# hardware_design.net
KiCad netlist of a schematic drawn in Altium Designer
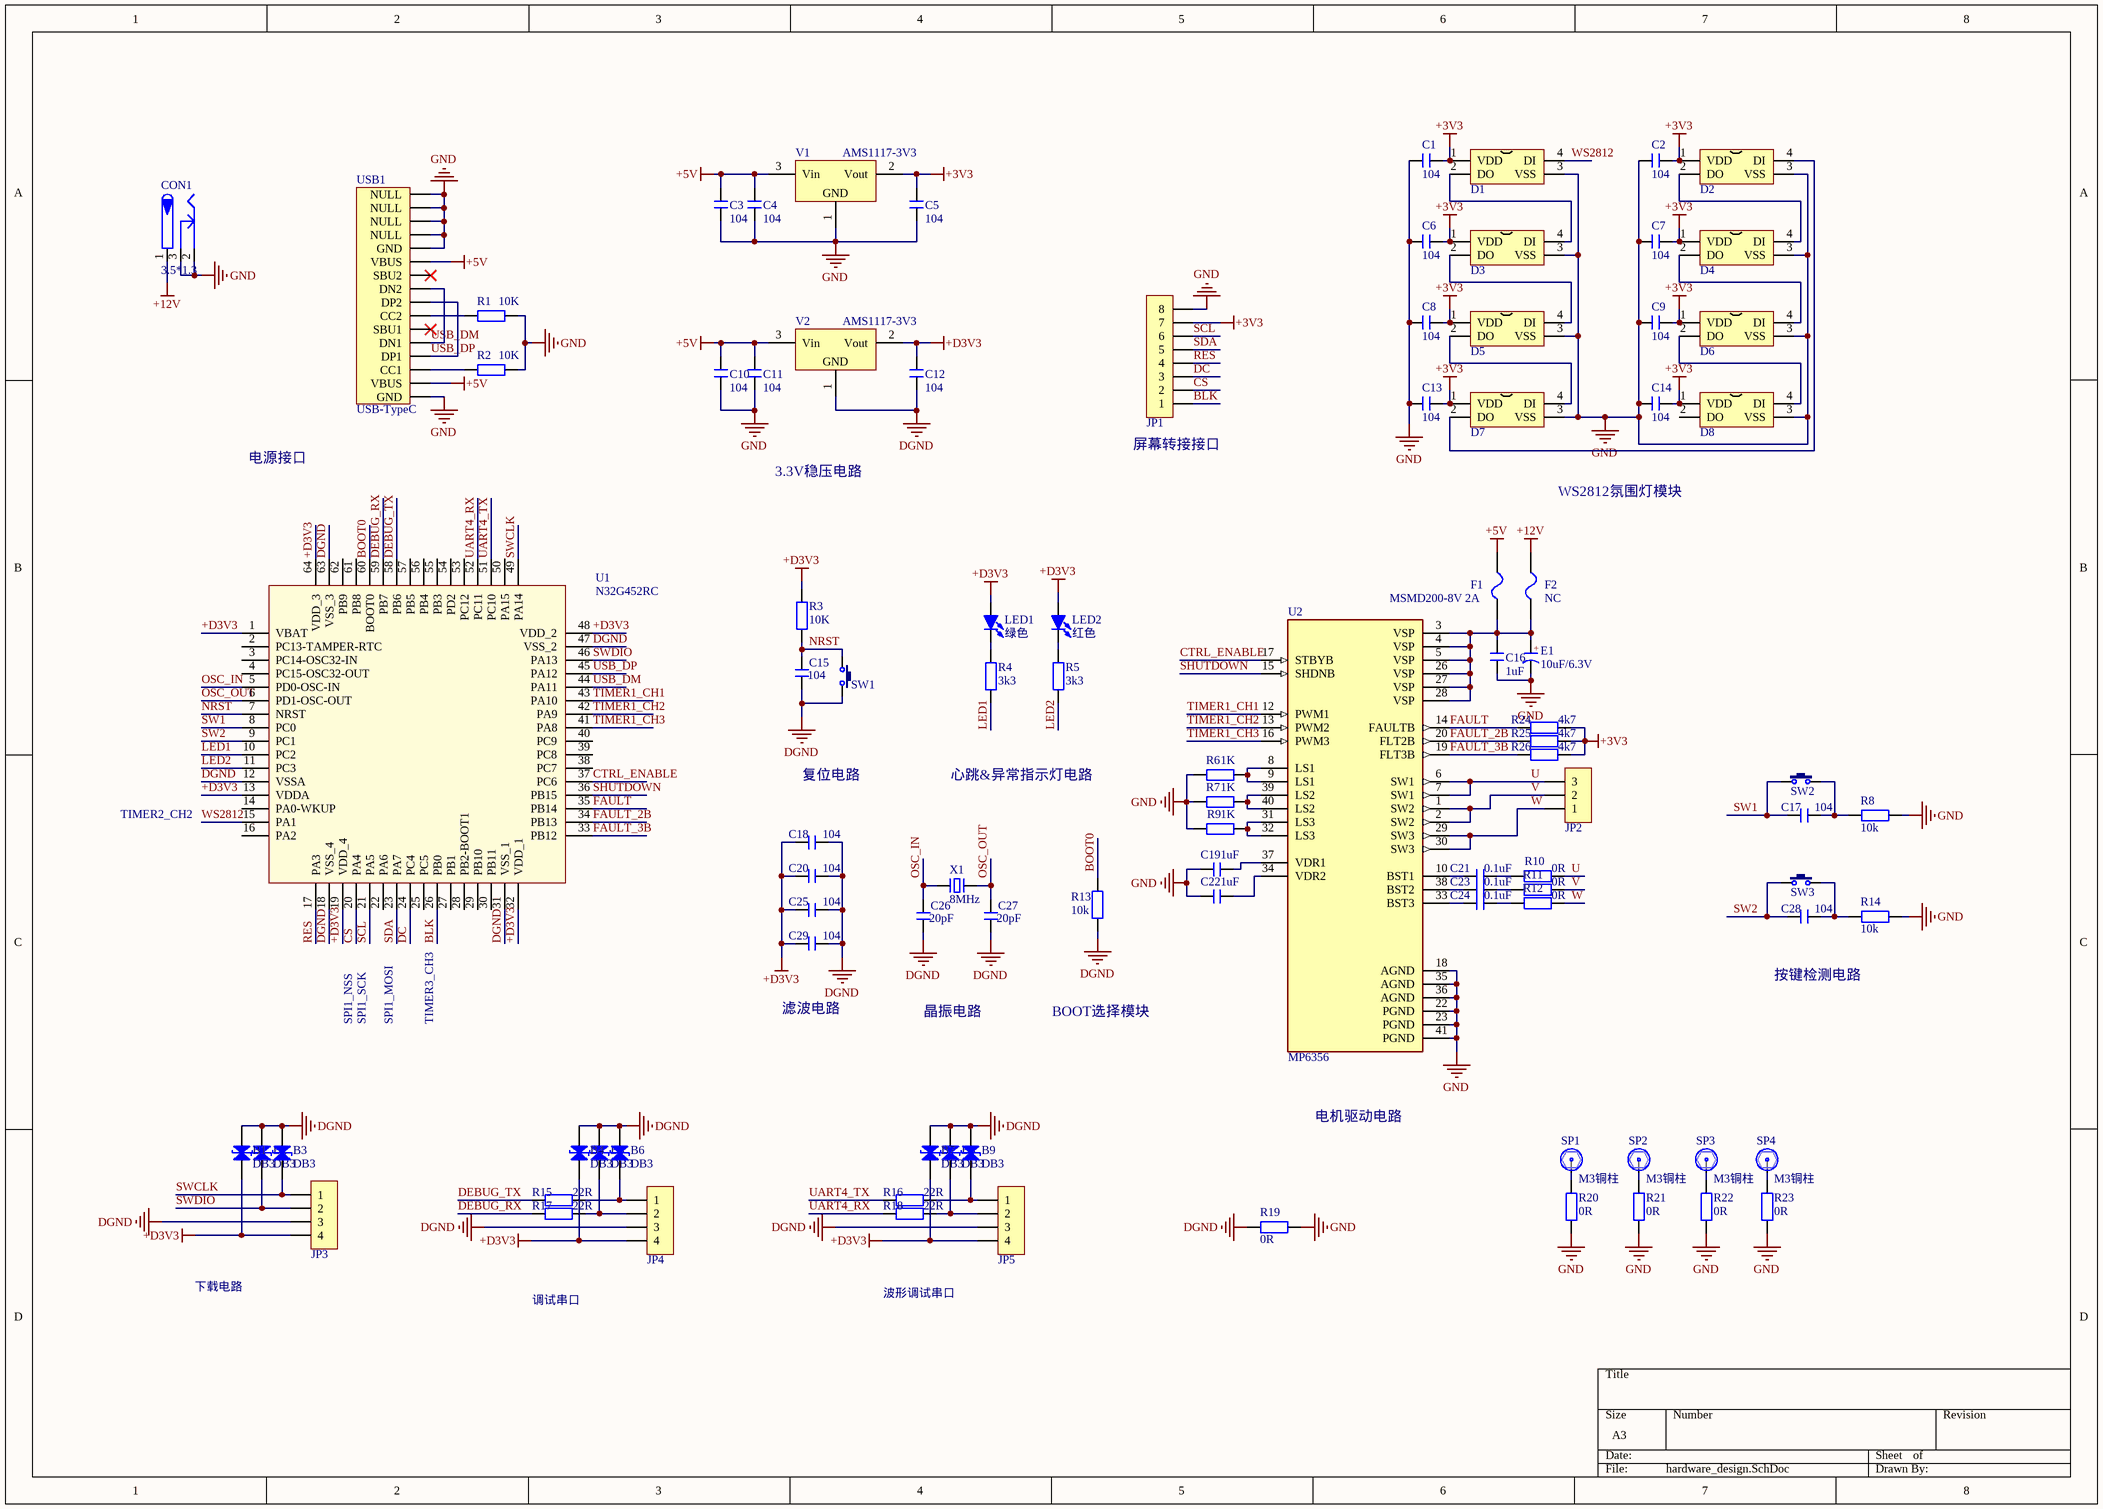
[diagram p0: hardware_design.SchDoc]

(export (version "E")
  (design (tool "Eeschema 10.0.6"))
  (components
    (comp (ref "B1")
      (value "DB3")
      (footprint "SOD-323")
      (description "双向触发二极管")
      (libsource (lib "8.1   - 二极管-整流桥") (part "DB3"))
    )
    (comp (ref "B2")
      (value "DB3")
      (footprint "SOD-323")
      (description "双向触发二极管")
      (libsource (lib "8.1   - 二极管-整流桥") (part "DB3"))
    )
    (comp (ref "B3")
      (value "DB3")
      (footprint "SOD-323")
      (description "双向触发二极管")
      (libsource (lib "8.1   - 二极管-整流桥") (part "DB3"))
    )
    (comp (ref "B4")
      (value "DB3")
      (footprint "SOD-323")
      (description "双向触发二极管")
      (libsource (lib "8.1   - 二极管-整流桥") (part "DB3"))
    )
    (comp (ref "B5")
      (value "DB3")
      (footprint "SOD-323")
      (description "双向触发二极管")
      (libsource (lib "8.1   - 二极管-整流桥") (part "DB3"))
    )
    (comp (ref "B6")
      (value "DB3")
      (footprint "SOD-323")
      (description "双向触发二极管")
      (libsource (lib "8.1   - 二极管-整流桥") (part "DB3"))
    )
    (comp (ref "B7")
      (value "DB3")
      (footprint "SOD-323")
      (description "双向触发二极管")
      (libsource (lib "8.1   - 二极管-整流桥") (part "DB3"))
    )
    (comp (ref "B8")
      (value "DB3")
      (footprint "SOD-323")
      (description "双向触发二极管")
      (libsource (lib "8.1   - 二极管-整流桥") (part "DB3"))
    )
    (comp (ref "B9")
      (value "DB3")
      (footprint "SOD-323")
      (description "双向触发二极管")
      (libsource (lib "8.1   - 二极管-整流桥") (part "DB3"))
    )
    (comp (ref "C1")
      (value "104")
      (footprint "C 0603_M")
      (description "无极性贴片电容")
      (fields (field (name "版权归属") "源创客"))
      (libsource (lib "3.1   - 电阻-电容-电感") (part "C"))
    )
    (comp (ref "C2")
      (value "104")
      (footprint "C 0603_M")
      (description "无极性贴片电容")
      (fields (field (name "版权归属") "源创客"))
      (libsource (lib "3.1   - 电阻-电容-电感") (part "C"))
    )
    (comp (ref "C3")
      (value "104")
      (footprint "C 0603_M")
      (description "无极性贴片电容")
      (fields (field (name "版权归属") "源创客"))
      (libsource (lib "3.1   - 电阻-电容-电感") (part "C"))
    )
    (comp (ref "C4")
      (value "104")
      (footprint "C 0603_M")
      (description "无极性贴片电容")
      (fields (field (name "版权归属") "源创客"))
      (libsource (lib "3.1   - 电阻-电容-电感") (part "C"))
    )
    (comp (ref "C5")
      (value "104")
      (footprint "C 0603_M")
      (description "无极性贴片电容")
      (fields (field (name "版权归属") "源创客"))
      (libsource (lib "3.1   - 电阻-电容-电感") (part "C"))
    )
    (comp (ref "C6")
      (value "104")
      (footprint "C 0603_M")
      (description "无极性贴片电容")
      (fields (field (name "版权归属") "源创客"))
      (libsource (lib "3.1   - 电阻-电容-电感") (part "C"))
    )
    (comp (ref "C7")
      (value "104")
      (footprint "C 0603_M")
      (description "无极性贴片电容")
      (fields (field (name "版权归属") "源创客"))
      (libsource (lib "3.1   - 电阻-电容-电感") (part "C"))
    )
    (comp (ref "C8")
      (value "104")
      (footprint "C 0603_M")
      (description "无极性贴片电容")
      (fields (field (name "版权归属") "源创客"))
      (libsource (lib "3.1   - 电阻-电容-电感") (part "C"))
    )
    (comp (ref "C9")
      (value "104")
      (footprint "C 0603_M")
      (description "无极性贴片电容")
      (fields (field (name "版权归属") "源创客"))
      (libsource (lib "3.1   - 电阻-电容-电感") (part "C"))
    )
    (comp (ref "C10")
      (value "104")
      (footprint "C 0603_M")
      (description "无极性贴片电容")
      (fields (field (name "版权归属") "源创客"))
      (libsource (lib "3.1   - 电阻-电容-电感") (part "C"))
    )
    (comp (ref "C11")
      (value "104")
      (footprint "C 0603_M")
      (description "无极性贴片电容")
      (fields (field (name "版权归属") "源创客"))
      (libsource (lib "3.1   - 电阻-电容-电感") (part "C"))
    )
    (comp (ref "C12")
      (value "104")
      (footprint "C 0603_M")
      (description "无极性贴片电容")
      (fields (field (name "版权归属") "源创客"))
      (libsource (lib "3.1   - 电阻-电容-电感") (part "C"))
    )
    (comp (ref "C13")
      (value "104")
      (footprint "C 0603_M")
      (description "无极性贴片电容")
      (fields (field (name "版权归属") "源创客"))
      (libsource (lib "3.1   - 电阻-电容-电感") (part "C"))
    )
    (comp (ref "C14")
      (value "104")
      (footprint "C 0603_M")
      (description "无极性贴片电容")
      (fields (field (name "版权归属") "源创客"))
      (libsource (lib "3.1   - 电阻-电容-电感") (part "C"))
    )
    (comp (ref "C15")
      (value "104")
      (footprint "C 0603_M")
      (description "无极性贴片电容")
      (fields (field (name "版权归属") "源创客"))
      (libsource (lib "3.1   - 电阻-电容-电感") (part "C"))
    )
    (comp (ref "C16")
      (value "1uF")
      (footprint "C 0603_M")
      (description "无极性贴片电容")
      (fields (field (name "版权归属") "源创客"))
      (libsource (lib "3.1   - 电阻-电容-电感") (part "C"))
    )
    (comp (ref "C17")
      (value "104")
      (footprint "C 0603_M")
      (description "无极性贴片电容")
      (fields (field (name "版权归属") "源创客"))
      (libsource (lib "3.1   - 电阻-电容-电感") (part "C"))
    )
    (comp (ref "C18")
      (value "104")
      (footprint "C 0603_M")
      (description "无极性贴片电容")
      (fields (field (name "版权归属") "源创客"))
      (libsource (lib "3.1   - 电阻-电容-电感") (part "C"))
    )
    (comp (ref "C19")
      (value "1uF")
      (footprint "C 0603_M")
      (description "无极性贴片电容")
      (fields (field (name "版权归属") "源创客"))
      (libsource (lib "3.1   - 电阻-电容-电感") (part "C"))
    )
    (comp (ref "C20")
      (value "104")
      (footprint "C 0603_M")
      (description "无极性贴片电容")
      (fields (field (name "版权归属") "源创客"))
      (libsource (lib "3.1   - 电阻-电容-电感") (part "C"))
    )
    (comp (ref "C21")
      (value "0.1uF")
      (footprint "C 0603_M")
      (description "无极性贴片电容")
      (fields (field (name "版权归属") "源创客"))
      (libsource (lib "3.1   - 电阻-电容-电感") (part "C"))
    )
    (comp (ref "C22")
      (value "1uF")
      (footprint "C 0603_M")
      (description "无极性贴片电容")
      (fields (field (name "版权归属") "源创客"))
      (libsource (lib "3.1   - 电阻-电容-电感") (part "C"))
    )
    (comp (ref "C23")
      (value "0.1uF")
      (footprint "C 0603_M")
      (description "无极性贴片电容")
      (fields (field (name "版权归属") "源创客"))
      (libsource (lib "3.1   - 电阻-电容-电感") (part "C"))
    )
    (comp (ref "C24")
      (value "0.1uF")
      (footprint "C 0603_M")
      (description "无极性贴片电容")
      (fields (field (name "版权归属") "源创客"))
      (libsource (lib "3.1   - 电阻-电容-电感") (part "C"))
    )
    (comp (ref "C25")
      (value "104")
      (footprint "C 0603_M")
      (description "无极性贴片电容")
      (fields (field (name "版权归属") "源创客"))
      (libsource (lib "3.1   - 电阻-电容-电感") (part "C"))
    )
    (comp (ref "C26")
      (value "20pF")
      (footprint "C 0603_M")
      (description "无极性贴片电容")
      (fields (field (name "版权归属") "源创客"))
      (libsource (lib "3.1   - 电阻-电容-电感") (part "C"))
    )
    (comp (ref "C27")
      (value "20pF")
      (footprint "C 0603_M")
      (description "无极性贴片电容")
      (fields (field (name "版权归属") "源创客"))
      (libsource (lib "3.1   - 电阻-电容-电感") (part "C"))
    )
    (comp (ref "C28")
      (value "104")
      (footprint "C 0603_M")
      (description "无极性贴片电容")
      (fields (field (name "版权归属") "源创客"))
      (libsource (lib "3.1   - 电阻-电容-电感") (part "C"))
    )
    (comp (ref "C29")
      (value "104")
      (footprint "C 0603_M")
      (description "无极性贴片电容")
      (fields (field (name "版权归属") "源创客"))
      (libsource (lib "3.1   - 电阻-电容-电感") (part "C"))
    )
    (comp (ref "CON1")
      (value "3.5*1.3")
      (footprint "DC-005")
      (description "低压电源接口")
      (fields (field (name "版权归属") "源创客"))
      (libsource (lib "4.1   - 接口类") (part "P-DC"))
    )
    (comp (ref "D1")
      (value "WS2812B")
      (footprint "WS2812 5050")
      (libsource (lib "9.1   - LED") (part "WS2812B"))
    )
    (comp (ref "D2")
      (value "WS2812B")
      (footprint "WS2812 5050")
      (libsource (lib "9.1   - LED") (part "WS2812B"))
    )
    (comp (ref "D3")
      (value "WS2812B")
      (footprint "WS2812 5050")
      (libsource (lib "9.1   - LED") (part "WS2812B"))
    )
    (comp (ref "D4")
      (value "WS2812B")
      (footprint "WS2812 5050")
      (libsource (lib "9.1   - LED") (part "WS2812B"))
    )
    (comp (ref "D5")
      (value "WS2812B")
      (footprint "WS2812 5050")
      (libsource (lib "9.1   - LED") (part "WS2812B"))
    )
    (comp (ref "D6")
      (value "WS2812B")
      (footprint "WS2812 5050")
      (libsource (lib "9.1   - LED") (part "WS2812B"))
    )
    (comp (ref "D7")
      (value "WS2812B")
      (footprint "WS2812 5050")
      (libsource (lib "9.1   - LED") (part "WS2812B"))
    )
    (comp (ref "D8")
      (value "WS2812B")
      (footprint "WS2812 5050")
      (libsource (lib "9.1   - LED") (part "WS2812B"))
    )
    (comp (ref "E1")
      (value "10uF/6.3V")
      (footprint "CD A(3216)")
      (description "贴片钽电容")
      (fields (field (name "版权归属") "源创客"))
      (libsource (lib "3.1   - 电阻-电容-电感") (part "C-CD"))
    )
    (comp (ref "F1")
      (value "MSMD200-8V 2A")
      (footprint "FU 1210")
      (description "贴片保险丝")
      (fields (field (name "版权归属") "源创客"))
      (libsource (lib "10.1 - 保险丝-晶振") (part "FU"))
    )
    (comp (ref "F2")
      (value "NC")
      (footprint "FU 1210")
      (description "贴片保险丝")
      (fields (field (name "版权归属") "源创客"))
      (libsource (lib "10.1 - 保险丝-晶振") (part "FU"))
    )
    (comp (ref "JP1")
      (value "HDR-1X8")
      (footprint "MX 1.25-WS-8P")
      (description "8P接插件")
      (fields (field (name "版权归属") "源创客"))
      (libsource (lib "4.2   - 接插件-脚距1.25") (part "Header 8"))
    )
    (comp (ref "JP2")
      (value "HDR-1X3")
      (footprint "XH2.54-WI-3P")
      (description "3P接插件")
      (fields (field (name "版权归属") "源创客"))
      (libsource (lib "4.5   - 接插件-脚距2.54") (part "Header 3"))
    )
    (comp (ref "JP3")
      (value "HDR-1X4")
      (footprint "MX 1.25-LS-4P")
      (description "4P接插件")
      (fields (field (name "版权归属") "源创客"))
      (libsource (lib "4.2   - 接插件-脚距1.25") (part "Header 4"))
    )
    (comp (ref "JP4")
      (value "HDR-1X4")
      (footprint "MX 1.25-LS-4P")
      (description "4P接插件")
      (fields (field (name "版权归属") "源创客"))
      (libsource (lib "4.2   - 接插件-脚距1.25") (part "Header 4"))
    )
    (comp (ref "JP5")
      (value "HDR-1X4")
      (footprint "MX 1.25-LS-4P")
      (description "4P接插件")
      (fields (field (name "版权归属") "源创客"))
      (libsource (lib "4.2   - 接插件-脚距1.25") (part "Header 4"))
    )
    (comp (ref "LED1")
      (value "绿色")
      (footprint "LED 0805W")
      (description "贴片LED")
      (fields (field (name "版权归属") "源创客"))
      (libsource (lib "9.1   - LED") (part "LED-SMD"))
    )
    (comp (ref "LED2")
      (value "红色")
      (footprint "LED 0805W")
      (description "贴片LED")
      (fields (field (name "版权归属") "源创客"))
      (libsource (lib "9.1   - LED") (part "LED-SMD"))
    )
    (comp (ref "R1")
      (value "10K")
      (footprint "R 0805_M")
      (description "贴片电阻")
      (fields (field (name "版权归属") "源创客"))
      (libsource (lib "3.1   - 电阻-电容-电感") (part "R"))
    )
    (comp (ref "R2")
      (value "10K")
      (footprint "R 0805_M")
      (description "贴片电阻")
      (fields (field (name "版权归属") "源创客"))
      (libsource (lib "3.1   - 电阻-电容-电感") (part "R"))
    )
    (comp (ref "R3")
      (value "10K")
      (footprint "R 0603_M")
      (description "贴片电阻")
      (fields (field (name "版权归属") "源创客"))
      (libsource (lib "3.1   - 电阻-电容-电感") (part "R"))
    )
    (comp (ref "R4")
      (value "3k3")
      (footprint "R 0603_M")
      (description "贴片电阻")
      (fields (field (name "版权归属") "源创客"))
      (libsource (lib "3.1   - 电阻-电容-电感") (part "R"))
    )
    (comp (ref "R5")
      (value "3k3")
      (footprint "R 0603_M")
      (description "贴片电阻")
      (fields (field (name "版权归属") "源创客"))
      (libsource (lib "3.1   - 电阻-电容-电感") (part "R"))
    )
    (comp (ref "R6")
      (value "1K")
      (footprint "R 1210_M")
      (description "贴片电阻")
      (fields (field (name "版权归属") "源创客"))
      (libsource (lib "3.1   - 电阻-电容-电感") (part "R"))
    )
    (comp (ref "R7")
      (value "1K")
      (footprint "R 1210_M")
      (description "贴片电阻")
      (fields (field (name "版权归属") "源创客"))
      (libsource (lib "3.1   - 电阻-电容-电感") (part "R"))
    )
    (comp (ref "R8")
      (value "10k")
      (footprint "R 0603_M")
      (description "贴片电阻")
      (fields (field (name "版权归属") "源创客"))
      (libsource (lib "3.1   - 电阻-电容-电感") (part "R"))
    )
    (comp (ref "R9")
      (value "1K")
      (footprint "R 1210_M")
      (description "贴片电阻")
      (fields (field (name "版权归属") "源创客"))
      (libsource (lib "3.1   - 电阻-电容-电感") (part "R"))
    )
    (comp (ref "R10")
      (value "0R")
      (footprint "R 0603_M")
      (description "贴片电阻")
      (fields (field (name "版权归属") "源创客"))
      (libsource (lib "3.1   - 电阻-电容-电感") (part "R"))
    )
    (comp (ref "R11")
      (value "0R")
      (footprint "R 0603_M")
      (description "贴片电阻")
      (fields (field (name "版权归属") "源创客"))
      (libsource (lib "3.1   - 电阻-电容-电感") (part "R"))
    )
    (comp (ref "R12")
      (value "0R")
      (footprint "R 0603_M")
      (description "贴片电阻")
      (fields (field (name "版权归属") "源创客"))
      (libsource (lib "3.1   - 电阻-电容-电感") (part "R"))
    )
    (comp (ref "R13")
      (value "10k")
      (footprint "R 0603_M")
      (description "贴片电阻")
      (fields (field (name "版权归属") "源创客"))
      (libsource (lib "3.1   - 电阻-电容-电感") (part "R"))
    )
    (comp (ref "R14")
      (value "10k")
      (footprint "R 0603_M")
      (description "贴片电阻")
      (fields (field (name "版权归属") "源创客"))
      (libsource (lib "3.1   - 电阻-电容-电感") (part "R"))
    )
    (comp (ref "R15")
      (value "22R")
      (footprint "R 0603_M")
      (description "贴片电阻")
      (fields (field (name "版权归属") "源创客"))
      (libsource (lib "3.1   - 电阻-电容-电感") (part "R"))
    )
    (comp (ref "R16")
      (value "22R")
      (footprint "R 0603_M")
      (description "贴片电阻")
      (fields (field (name "版权归属") "源创客"))
      (libsource (lib "3.1   - 电阻-电容-电感") (part "R"))
    )
    (comp (ref "R17")
      (value "22R")
      (footprint "R 0603_M")
      (description "贴片电阻")
      (fields (field (name "版权归属") "源创客"))
      (libsource (lib "3.1   - 电阻-电容-电感") (part "R"))
    )
    (comp (ref "R18")
      (value "22R")
      (footprint "R 0603_M")
      (description "贴片电阻")
      (fields (field (name "版权归属") "源创客"))
      (libsource (lib "3.1   - 电阻-电容-电感") (part "R"))
    )
    (comp (ref "R19")
      (value "0R")
      (footprint "R 0603_M")
      (description "贴片电阻")
      (fields (field (name "版权归属") "源创客"))
      (libsource (lib "3.1   - 电阻-电容-电感") (part "R"))
    )
    (comp (ref "R20")
      (value "0R")
      (footprint "R 0603_M")
      (description "贴片电阻")
      (fields (field (name "版权归属") "源创客"))
      (libsource (lib "3.1   - 电阻-电容-电感") (part "R"))
    )
    (comp (ref "R21")
      (value "0R")
      (footprint "R 0603_M")
      (description "贴片电阻")
      (fields (field (name "版权归属") "源创客"))
      (libsource (lib "3.1   - 电阻-电容-电感") (part "R"))
    )
    (comp (ref "R22")
      (value "0R")
      (footprint "R 0603_M")
      (description "贴片电阻")
      (fields (field (name "版权归属") "源创客"))
      (libsource (lib "3.1   - 电阻-电容-电感") (part "R"))
    )
    (comp (ref "R23")
      (value "0R")
      (footprint "R 0603_M")
      (description "贴片电阻")
      (fields (field (name "版权归属") "源创客"))
      (libsource (lib "3.1   - 电阻-电容-电感") (part "R"))
    )
    (comp (ref "R24")
      (value "4k7")
      (footprint "R 0603_M")
      (description "贴片电阻")
      (fields (field (name "版权归属") "源创客"))
      (libsource (lib "3.1   - 电阻-电容-电感") (part "R"))
    )
    (comp (ref "R25")
      (value "4k7")
      (footprint "R 0603_M")
      (description "贴片电阻")
      (fields (field (name "版权归属") "源创客"))
      (libsource (lib "3.1   - 电阻-电容-电感") (part "R"))
    )
    (comp (ref "R26")
      (value "4k7")
      (footprint "R 0603_M")
      (description "贴片电阻")
      (fields (field (name "版权归属") "源创客"))
      (libsource (lib "3.1   - 电阻-电容-电感") (part "R"))
    )
    (comp (ref "SP1")
      (value "M3铜柱")
      (footprint "M3x4_L")
      (description "铜柱")
      (fields (field (name "版权归属") "源创客"))
      (libsource (lib "library") (part "铜柱小焊盘"))
    )
    (comp (ref "SP2")
      (value "M3铜柱")
      (footprint "M3x4_L")
      (description "铜柱")
      (fields (field (name "版权归属") "源创客"))
      (libsource (lib "library") (part "铜柱小焊盘"))
    )
    (comp (ref "SP3")
      (value "M3铜柱")
      (footprint "M3x4_L")
      (description "铜柱")
      (fields (field (name "版权归属") "源创客"))
      (libsource (lib "library") (part "铜柱小焊盘"))
    )
    (comp (ref "SP4")
      (value "M3铜柱")
      (footprint "M3x4_L")
      (description "铜柱")
      (fields (field (name "版权归属") "源创客"))
      (libsource (lib "library") (part "铜柱小焊盘"))
    )
    (comp (ref "SW1")
      (value "3x6x5")
      (footprint "TSW SMD-3*6*2.5")
      (description "3x6轻触开关")
      (fields (field (name "版权归属") "源创客"))
      (libsource (lib "5.1   - 按键-开关") (part "TSW 3x6"))
    )
    (comp (ref "SW2")
      (value "3x6x5")
      (footprint "TSW SMD-3*6*2.5")
      (description "3x6轻触开关")
      (fields (field (name "版权归属") "源创客"))
      (libsource (lib "") (part "TSW 3x6_1"))
    )
    (comp (ref "SW3")
      (value "3x6x5")
      (footprint "TSW SMD-3*6*2.5")
      (description "3x6轻触开关")
      (fields (field (name "版权归属") "源创客"))
      (libsource (lib "") (part "TSW 3x6_1"))
    )
    (comp (ref "U1")
      (value "N32G452RC")
      (footprint "LQFP64-10*10")
      (description "国民技术32位mcu IO64")
      (libsource (lib "library") (part "N32G452RC"))
    )
    (comp (ref "U2")
      (value "MP6356")
      (footprint "QFN40（5x5mm）")
      (description "直流无刷电机驱动IC")
      (libsource (lib "library") (part "MP6536DU-LF-P"))
    )
    (comp (ref "USB1")
      (value "USB-TypeC")
      (footprint "USB-TypeC-16Pin")
      (description "TypeC 16pin")
      (libsource (lib "library") (part "USB-TypeC-16Pin"))
    )
    (comp (ref "V1")
      (value "AMS1117-3V3")
      (footprint "SOT223_M")
      (description "三端稳压芯片")
      (fields (field (name "版权归属") "源创客"))
      (libsource (lib "1.3   - 电源类芯片") (part "AMS1117"))
    )
    (comp (ref "V2")
      (value "AMS1117-3V3")
      (footprint "SOT223_M")
      (description "三端稳压芯片")
      (fields (field (name "版权归属") "源创客"))
      (libsource (lib "1.3   - 电源类芯片") (part "AMS1117"))
    )
    (comp (ref "X1")
      (value "8MHz")
      (footprint "OSC HC-49SMD")
      (description "2脚无源脚晶振")
      (fields (field (name "版权归属") "源创客"))
      (libsource (lib "10.1 - 保险丝-晶振") (part "XTAL-2P"))
    )
  )
  (nets
    (net (code "1") (name "+3V3") (class "Default")
      (node (ref "C1") (pin "1") (pinfunction "1_1") (pintype "passive"))
      (node (ref "C13") (pin "1") (pinfunction "1_1") (pintype "passive"))
      (node (ref "C14") (pin "1") (pinfunction "1_1") (pintype "passive"))
      (node (ref "C2") (pin "1") (pinfunction "1_1") (pintype "passive"))
      (node (ref "C5") (pin "1") (pinfunction "1_1") (pintype "passive"))
      (node (ref "C6") (pin "1") (pinfunction "1_1") (pintype "passive"))
      (node (ref "C7") (pin "1") (pinfunction "1_1") (pintype "passive"))
      (node (ref "C8") (pin "1") (pinfunction "1_1") (pintype "passive"))
      (node (ref "C9") (pin "1") (pinfunction "1_1") (pintype "passive"))
      (node (ref "D1") (pin "1") (pinfunction "VDD_1") (pintype "passive"))
      (node (ref "D2") (pin "1") (pinfunction "VDD_1") (pintype "passive"))
      (node (ref "D3") (pin "1") (pinfunction "VDD_1") (pintype "passive"))
      (node (ref "D4") (pin "1") (pinfunction "VDD_1") (pintype "passive"))
      (node (ref "D5") (pin "1") (pinfunction "VDD_1") (pintype "passive"))
      (node (ref "D6") (pin "1") (pinfunction "VDD_1") (pintype "passive"))
      (node (ref "D7") (pin "1") (pinfunction "VDD_1") (pintype "passive"))
      (node (ref "D8") (pin "1") (pinfunction "VDD_1") (pintype "passive"))
      (node (ref "JP1") (pin "7") (pinfunction "7_7") (pintype "passive"))
      (node (ref "R24") (pin "2") (pinfunction "2_2") (pintype "passive"))
      (node (ref "R25") (pin "2") (pinfunction "2_2") (pintype "passive"))
      (node (ref "R26") (pin "2") (pinfunction "2_2") (pintype "passive"))
      (node (ref "V1") (pin "2") (pinfunction "Vout_2") (pintype "passive"))
    )
    (net (code "2") (name "+5V") (class "Default")
      (node (ref "C10") (pin "1") (pinfunction "1_1") (pintype "passive"))
      (node (ref "C11") (pin "1") (pinfunction "1_1") (pintype "passive"))
      (node (ref "C3") (pin "1") (pinfunction "1_1") (pintype "passive"))
      (node (ref "C4") (pin "1") (pinfunction "1_1") (pintype "passive"))
      (node (ref "F1") (pin "1") (pinfunction "1_1") (pintype "passive"))
      (node (ref "USB1") (pin "A4B9") (pinfunction "VBUS_A4B9") (pintype "passive"))
      (node (ref "USB1") (pin "B4A9") (pinfunction "VBUS_B4A9") (pintype "passive"))
      (node (ref "V1") (pin "3") (pinfunction "Vin_3") (pintype "passive"))
      (node (ref "V2") (pin "3") (pinfunction "Vin_3") (pintype "passive"))
    )
    (net (code "3") (name "+12V") (class "Default")
      (node (ref "CON1") (pin "1") (pintype "power_in"))
      (node (ref "F2") (pin "2") (pinfunction "2_2") (pintype "passive"))
    )
    (net (code "4") (name "+D3V3") (class "Default")
      (node (ref "B1") (pin "2") (pinfunction "K_2") (pintype "passive"))
      (node (ref "B4") (pin "2") (pinfunction "K_2") (pintype "passive"))
      (node (ref "B7") (pin "2") (pinfunction "K_2") (pintype "passive"))
      (node (ref "C12") (pin "1") (pinfunction "1_1") (pintype "passive"))
      (node (ref "C18") (pin "2") (pinfunction "2_2") (pintype "passive"))
      (node (ref "C20") (pin "2") (pinfunction "2_2") (pintype "passive"))
      (node (ref "C25") (pin "2") (pinfunction "2_2") (pintype "passive"))
      (node (ref "C29") (pin "2") (pinfunction "2_2") (pintype "passive"))
      (node (ref "JP3") (pin "4") (pinfunction "4_4") (pintype "passive"))
      (node (ref "JP4") (pin "4") (pinfunction "4_4") (pintype "passive"))
      (node (ref "JP5") (pin "4") (pinfunction "4_4") (pintype "passive"))
      (node (ref "LED1") (pin "1") (pinfunction "A_1") (pintype "passive"))
      (node (ref "LED2") (pin "1") (pinfunction "A_1") (pintype "passive"))
      (node (ref "R3") (pin "2") (pinfunction "2_2") (pintype "passive"))
      (node (ref "U1") (pin "1") (pinfunction "VBAT_1") (pintype "passive"))
      (node (ref "U1") (pin "13") (pinfunction "VDDA_13") (pintype "passive"))
      (node (ref "U1") (pin "19") (pinfunction "VDD_4_19") (pintype "passive"))
      (node (ref "U1") (pin "32") (pinfunction "VDD_1_32") (pintype "passive"))
      (node (ref "U1") (pin "48") (pinfunction "VDD_2_48") (pintype "passive"))
      (node (ref "U1") (pin "64") (pinfunction "VDD_3_64") (pintype "passive"))
      (node (ref "V2") (pin "2") (pinfunction "Vout_2") (pintype "passive"))
    )
    (net (code "5") (name "/BLK") (class "Default")
      (node (ref "JP1") (pin "1") (pinfunction "1_1") (pintype "passive"))
      (node (ref "U1") (pin "26") (pinfunction "PB0_26") (pintype "passive"))
    )
    (net (code "6") (name "/BOOT0") (class "Default")
      (node (ref "R13") (pin "2") (pinfunction "2_2") (pintype "passive"))
      (node (ref "U1") (pin "60") (pinfunction "BOOT0_60") (pintype "passive"))
    )
    (net (code "7") (name "/CS") (class "Default")
      (node (ref "JP1") (pin "2") (pinfunction "2_2") (pintype "passive"))
      (node (ref "U1") (pin "20") (pinfunction "PA4_20") (pintype "passive"))
    )
    (net (code "8") (name "/CTRL_ENABLE") (class "Default")
      (node (ref "U1") (pin "37") (pinfunction "PC6_37") (pintype "passive"))
      (node (ref "U2") (pin "17") (pinfunction "STBYB_17") (pintype "input"))
    )
    (net (code "9") (name "/DC") (class "Default")
      (node (ref "JP1") (pin "3") (pinfunction "3_3") (pintype "passive"))
      (node (ref "U1") (pin "24") (pinfunction "PC4_24") (pintype "passive"))
    )
    (net (code "10") (name "/DEBUG_RX") (class "Default")
      (node (ref "R17") (pin "1") (pinfunction "1_1") (pintype "passive"))
      (node (ref "U1") (pin "59") (pinfunction "PB7_59") (pintype "passive"))
    )
    (net (code "11") (name "/DEBUG_TX") (class "Default")
      (node (ref "R15") (pin "1") (pinfunction "1_1") (pintype "passive"))
      (node (ref "U1") (pin "58") (pinfunction "PB6_58") (pintype "passive"))
    )
    (net (code "12") (name "/FAULT") (class "Default")
      (node (ref "R24") (pin "1") (pinfunction "1_1") (pintype "passive"))
      (node (ref "U1") (pin "35") (pinfunction "PB14_35") (pintype "passive"))
      (node (ref "U2") (pin "14") (pinfunction "FAULTB_14") (pintype "output"))
    )
    (net (code "13") (name "/FAULT_2B") (class "Default")
      (node (ref "R25") (pin "1") (pinfunction "1_1") (pintype "passive"))
      (node (ref "U1") (pin "34") (pinfunction "PB13_34") (pintype "passive"))
      (node (ref "U2") (pin "20") (pinfunction "FLT2B_20") (pintype "output"))
    )
    (net (code "14") (name "/FAULT_3B") (class "Default")
      (node (ref "R26") (pin "1") (pinfunction "1_1") (pintype "passive"))
      (node (ref "U1") (pin "33") (pinfunction "PB12_33") (pintype "passive"))
      (node (ref "U2") (pin "19") (pinfunction "FLT3B_19") (pintype "output"))
    )
    (net (code "15") (name "/LED1") (class "Default")
      (node (ref "R4") (pin "1") (pinfunction "1_1") (pintype "passive"))
      (node (ref "U1") (pin "10") (pinfunction "PC2_10") (pintype "passive"))
    )
    (net (code "16") (name "/LED2") (class "Default")
      (node (ref "R5") (pin "1") (pinfunction "1_1") (pintype "passive"))
      (node (ref "U1") (pin "11") (pinfunction "PC3_11") (pintype "passive"))
    )
    (net (code "17") (name "/NRST") (class "Default")
      (node (ref "C15") (pin "2") (pinfunction "2_2") (pintype "passive"))
      (node (ref "R3") (pin "1") (pinfunction "1_1") (pintype "passive"))
      (node (ref "SW1") (pin "1") (pinfunction "1_1") (pintype "passive"))
      (node (ref "U1") (pin "7") (pinfunction "NRST_7") (pintype "passive"))
    )
    (net (code "18") (name "/OSC_IN") (class "Default")
      (node (ref "C26") (pin "2") (pinfunction "2_2") (pintype "passive"))
      (node (ref "U1") (pin "5") (pinfunction "PD0-OSC-IN_5") (pintype "passive"))
      (node (ref "X1") (pin "1") (pinfunction "1_1") (pintype "passive"))
    )
    (net (code "19") (name "/OSC_OUT") (class "Default")
      (node (ref "C27") (pin "2") (pinfunction "2_2") (pintype "passive"))
      (node (ref "U1") (pin "6") (pinfunction "PD1-OSC-OUT_6") (pintype "passive"))
      (node (ref "X1") (pin "2") (pinfunction "2_2") (pintype "passive"))
    )
    (net (code "20") (name "/RES") (class "Default")
      (node (ref "JP1") (pin "4") (pinfunction "4_4") (pintype "passive"))
      (node (ref "U1") (pin "17") (pinfunction "PA3_17") (pintype "passive"))
    )
    (net (code "21") (name "/SCL") (class "Default")
      (node (ref "JP1") (pin "6") (pinfunction "6_6") (pintype "passive"))
      (node (ref "U1") (pin "21") (pinfunction "PA5_21") (pintype "passive"))
    )
    (net (code "22") (name "/SDA") (class "Default")
      (node (ref "JP1") (pin "5") (pinfunction "5_5") (pintype "passive"))
      (node (ref "U1") (pin "23") (pinfunction "PA7_23") (pintype "passive"))
    )
    (net (code "23") (name "/SHUTDOWN") (class "Default")
      (node (ref "U1") (pin "36") (pinfunction "PB15_36") (pintype "passive"))
      (node (ref "U2") (pin "15") (pinfunction "SHDNB_15") (pintype "input"))
    )
    (net (code "24") (name "/SW1") (class "Default")
      (node (ref "C17") (pin "2") (pinfunction "2_2") (pintype "passive"))
      (node (ref "SW2") (pin "1") (pinfunction "1_1") (pintype "passive"))
      (node (ref "U1") (pin "8") (pinfunction "PC0_8") (pintype "passive"))
    )
    (net (code "25") (name "/SW2") (class "Default")
      (node (ref "C28") (pin "2") (pinfunction "2_2") (pintype "passive"))
      (node (ref "SW3") (pin "1") (pinfunction "1_1") (pintype "passive"))
      (node (ref "U1") (pin "9") (pinfunction "PC1_9") (pintype "passive"))
    )
    (net (code "26") (name "/SWCLK") (class "Default")
      (node (ref "B3") (pin "2") (pinfunction "K_2") (pintype "passive"))
      (node (ref "JP3") (pin "1") (pinfunction "1_1") (pintype "passive"))
      (node (ref "U1") (pin "49") (pinfunction "PA14_49") (pintype "passive"))
    )
    (net (code "27") (name "/SWDIO") (class "Default")
      (node (ref "B2") (pin "2") (pinfunction "K_2") (pintype "passive"))
      (node (ref "JP3") (pin "2") (pinfunction "2_2") (pintype "passive"))
      (node (ref "U1") (pin "46") (pinfunction "PA13_46") (pintype "passive"))
    )
    (net (code "28") (name "/TIMER1_CH1") (class "Default")
      (node (ref "U1") (pin "43") (pinfunction "PA10_43") (pintype "passive"))
      (node (ref "U2") (pin "12") (pinfunction "PWM1_12") (pintype "input"))
    )
    (net (code "29") (name "/TIMER1_CH2") (class "Default")
      (node (ref "U1") (pin "42") (pinfunction "PA9_42") (pintype "passive"))
      (node (ref "U2") (pin "13") (pinfunction "PWM2_13") (pintype "input"))
    )
    (net (code "30") (name "/TIMER1_CH3") (class "Default")
      (node (ref "U1") (pin "41") (pinfunction "PA8_41") (pintype "passive"))
      (node (ref "U2") (pin "16") (pinfunction "PWM3_16") (pintype "input"))
    )
    (net (code "31") (name "/U") (class "Default")
      (node (ref "JP2") (pin "3") (pinfunction "3_3") (pintype "passive"))
      (node (ref "R10") (pin "2") (pinfunction "2_2") (pintype "passive"))
      (node (ref "U2") (pin "6") (pinfunction "SW1_6") (pintype "output"))
      (node (ref "U2") (pin "7") (pinfunction "SW1_7") (pintype "output"))
    )
    (net (code "32") (name "/UART4_RX") (class "Default")
      (node (ref "R18") (pin "1") (pinfunction "1_1") (pintype "passive"))
      (node (ref "U1") (pin "52") (pinfunction "PC11_52") (pintype "passive"))
    )
    (net (code "33") (name "/UART4_TX") (class "Default")
      (node (ref "R16") (pin "1") (pinfunction "1_1") (pintype "passive"))
      (node (ref "U1") (pin "51") (pinfunction "PC10_51") (pintype "passive"))
    )
    (net (code "34") (name "/USB_DM") (class "Default")
      (node (ref "U1") (pin "44") (pinfunction "PA11_44") (pintype "passive"))
      (node (ref "USB1") (pin "A7") (pinfunction "DN1_A7") (pintype "passive"))
      (node (ref "USB1") (pin "B7") (pinfunction "DN2_B7") (pintype "passive"))
    )
    (net (code "35") (name "/USB_DP") (class "Default")
      (node (ref "U1") (pin "45") (pinfunction "PA12_45") (pintype "passive"))
      (node (ref "USB1") (pin "A6") (pinfunction "DP1_A6") (pintype "passive"))
      (node (ref "USB1") (pin "B6") (pinfunction "DP2_B6") (pintype "passive"))
    )
    (net (code "36") (name "/V") (class "Default")
      (node (ref "JP2") (pin "2") (pinfunction "2_2") (pintype "passive"))
      (node (ref "R11") (pin "2") (pinfunction "2_2") (pintype "passive"))
      (node (ref "U2") (pin "1") (pinfunction "SW2_1") (pintype "output"))
      (node (ref "U2") (pin "2") (pinfunction "SW2_2") (pintype "output"))
    )
    (net (code "37") (name "/W") (class "Default")
      (node (ref "JP2") (pin "1") (pinfunction "1_1") (pintype "passive"))
      (node (ref "R12") (pin "2") (pinfunction "2_2") (pintype "passive"))
      (node (ref "U2") (pin "29") (pinfunction "SW3_29") (pintype "output"))
      (node (ref "U2") (pin "30") (pinfunction "SW3_30") (pintype "output"))
    )
    (net (code "38") (name "/WS2812") (class "Default")
      (node (ref "D1") (pin "4") (pinfunction "DI_4") (pintype "passive"))
      (node (ref "U1") (pin "15") (pinfunction "PA1_15") (pintype "passive"))
    )
    (net (code "39") (name "DGND") (class "Default")
      (node (ref "B1") (pin "1") (pinfunction "A_1") (pintype "passive"))
      (node (ref "B2") (pin "1") (pinfunction "A_1") (pintype "passive"))
      (node (ref "B3") (pin "1") (pinfunction "A_1") (pintype "passive"))
      (node (ref "B4") (pin "1") (pinfunction "A_1") (pintype "passive"))
      (node (ref "B5") (pin "1") (pinfunction "A_1") (pintype "passive"))
      (node (ref "B6") (pin "1") (pinfunction "A_1") (pintype "passive"))
      (node (ref "B7") (pin "1") (pinfunction "A_1") (pintype "passive"))
      (node (ref "B8") (pin "1") (pinfunction "A_1") (pintype "passive"))
      (node (ref "B9") (pin "1") (pinfunction "A_1") (pintype "passive"))
      (node (ref "C12") (pin "2") (pinfunction "2_2") (pintype "passive"))
      (node (ref "C15") (pin "1") (pinfunction "1_1") (pintype "passive"))
      (node (ref "C18") (pin "1") (pinfunction "1_1") (pintype "passive"))
      (node (ref "C20") (pin "1") (pinfunction "1_1") (pintype "passive"))
      (node (ref "C25") (pin "1") (pinfunction "1_1") (pintype "passive"))
      (node (ref "C26") (pin "1") (pinfunction "1_1") (pintype "passive"))
      (node (ref "C27") (pin "1") (pinfunction "1_1") (pintype "passive"))
      (node (ref "C29") (pin "1") (pinfunction "1_1") (pintype "passive"))
      (node (ref "JP3") (pin "3") (pinfunction "3_3") (pintype "passive"))
      (node (ref "JP4") (pin "3") (pinfunction "3_3") (pintype "passive"))
      (node (ref "JP5") (pin "3") (pinfunction "3_3") (pintype "passive"))
      (node (ref "R13") (pin "1") (pinfunction "1_1") (pintype "passive"))
      (node (ref "R19") (pin "1") (pinfunction "1_1") (pintype "passive"))
      (node (ref "SW1") (pin "2") (pinfunction "2_2") (pintype "passive"))
      (node (ref "U1") (pin "12") (pinfunction "VSSA_12") (pintype "passive"))
      (node (ref "U1") (pin "18") (pinfunction "VSS_4_18") (pintype "passive"))
      (node (ref "U1") (pin "31") (pinfunction "VSS_1_31") (pintype "passive"))
      (node (ref "U1") (pin "47") (pinfunction "VSS_2_47") (pintype "passive"))
      (node (ref "U1") (pin "63") (pinfunction "VSS_3_63") (pintype "passive"))
      (node (ref "V2") (pin "1") (pinfunction "GND_1") (pintype "passive"))
    )
    (net (code "40") (name "GND") (class "Default")
      (node (ref "C1") (pin "2") (pinfunction "2_2") (pintype "passive"))
      (node (ref "C10") (pin "2") (pinfunction "2_2") (pintype "passive"))
      (node (ref "C11") (pin "2") (pinfunction "2_2") (pintype "passive"))
      (node (ref "C13") (pin "2") (pinfunction "2_2") (pintype "passive"))
      (node (ref "C14") (pin "2") (pinfunction "2_2") (pintype "passive"))
      (node (ref "C16") (pin "2") (pinfunction "2_2") (pintype "passive"))
      (node (ref "C19") (pin "1") (pinfunction "1_1") (pintype "passive"))
      (node (ref "C2") (pin "2") (pinfunction "2_2") (pintype "passive"))
      (node (ref "C22") (pin "1") (pinfunction "1_1") (pintype "passive"))
      (node (ref "C3") (pin "2") (pinfunction "2_2") (pintype "passive"))
      (node (ref "C4") (pin "2") (pinfunction "2_2") (pintype "passive"))
      (node (ref "C5") (pin "2") (pinfunction "2_2") (pintype "passive"))
      (node (ref "C6") (pin "2") (pinfunction "2_2") (pintype "passive"))
      (node (ref "C7") (pin "2") (pinfunction "2_2") (pintype "passive"))
      (node (ref "C8") (pin "2") (pinfunction "2_2") (pintype "passive"))
      (node (ref "C9") (pin "2") (pinfunction "2_2") (pintype "passive"))
      (node (ref "CON1") (pin "2") (pintype "power_in"))
      (node (ref "CON1") (pin "3") (pintype "power_in"))
      (node (ref "D1") (pin "3") (pinfunction "VSS_3") (pintype "passive"))
      (node (ref "D2") (pin "3") (pinfunction "VSS_3") (pintype "passive"))
      (node (ref "D3") (pin "3") (pinfunction "VSS_3") (pintype "passive"))
      (node (ref "D4") (pin "3") (pinfunction "VSS_3") (pintype "passive"))
      (node (ref "D5") (pin "3") (pinfunction "VSS_3") (pintype "passive"))
      (node (ref "D6") (pin "3") (pinfunction "VSS_3") (pintype "passive"))
      (node (ref "D7") (pin "3") (pinfunction "VSS_3") (pintype "passive"))
      (node (ref "D8") (pin "3") (pinfunction "VSS_3") (pintype "passive"))
      (node (ref "E1") (pin "2") (pinfunction "K_2") (pintype "passive"))
      (node (ref "JP1") (pin "8") (pinfunction "8_8") (pintype "passive"))
      (node (ref "R1") (pin "2") (pinfunction "2_2") (pintype "passive"))
      (node (ref "R14") (pin "1") (pinfunction "1_1") (pintype "passive"))
      (node (ref "R19") (pin "2") (pinfunction "2_2") (pintype "passive"))
      (node (ref "R2") (pin "2") (pinfunction "2_2") (pintype "passive"))
      (node (ref "R20") (pin "2") (pinfunction "2_2") (pintype "passive"))
      (node (ref "R21") (pin "2") (pinfunction "2_2") (pintype "passive"))
      (node (ref "R22") (pin "2") (pinfunction "2_2") (pintype "passive"))
      (node (ref "R23") (pin "2") (pinfunction "2_2") (pintype "passive"))
      (node (ref "R6") (pin "1") (pinfunction "1_1") (pintype "passive"))
      (node (ref "R7") (pin "1") (pinfunction "1_1") (pintype "passive"))
      (node (ref "R8") (pin "1") (pinfunction "1_1") (pintype "passive"))
      (node (ref "R9") (pin "1") (pinfunction "1_1") (pintype "passive"))
      (node (ref "U2") (pin "18") (pinfunction "AGND_18") (pintype "power_in"))
      (node (ref "U2") (pin "22") (pinfunction "PGND_22") (pintype "power_in"))
      (node (ref "U2") (pin "23") (pinfunction "PGND_23") (pintype "power_in"))
      (node (ref "U2") (pin "35") (pinfunction "AGND_35") (pintype "power_in"))
      (node (ref "U2") (pin "36") (pinfunction "AGND_36") (pintype "power_in"))
      (node (ref "U2") (pin "41") (pinfunction "PGND_41") (pintype "power_in"))
      (node (ref "USB1") (pin "1") (pinfunction "NULL_1") (pintype "passive"))
      (node (ref "USB1") (pin "2") (pinfunction "NULL_2") (pintype "passive"))
      (node (ref "USB1") (pin "3") (pinfunction "NULL_3") (pintype "passive"))
      (node (ref "USB1") (pin "4") (pinfunction "NULL_4") (pintype "passive"))
      (node (ref "USB1") (pin "A1B12") (pinfunction "GND_A1B12") (pintype "passive"))
      (node (ref "USB1") (pin "B1A12") (pinfunction "GND_B1A12") (pintype "passive"))
      (node (ref "V1") (pin "1") (pinfunction "GND_1") (pintype "passive"))
    )
    (net (code "41") (name "Net-(B5-K)") (class "Default")
      (node (ref "B5") (pin "2") (pinfunction "K_2") (pintype "passive"))
      (node (ref "JP4") (pin "2") (pinfunction "2_2") (pintype "passive"))
      (node (ref "R17") (pin "2") (pinfunction "2_2") (pintype "passive"))
    )
    (net (code "42") (name "Net-(B6-K)") (class "Default")
      (node (ref "B6") (pin "2") (pinfunction "K_2") (pintype "passive"))
      (node (ref "JP4") (pin "1") (pinfunction "1_1") (pintype "passive"))
      (node (ref "R15") (pin "2") (pinfunction "2_2") (pintype "passive"))
    )
    (net (code "43") (name "Net-(B8-K)") (class "Default")
      (node (ref "B8") (pin "2") (pinfunction "K_2") (pintype "passive"))
      (node (ref "JP5") (pin "2") (pinfunction "2_2") (pintype "passive"))
      (node (ref "R18") (pin "2") (pinfunction "2_2") (pintype "passive"))
    )
    (net (code "44") (name "Net-(B9-K)") (class "Default")
      (node (ref "B9") (pin "2") (pinfunction "K_2") (pintype "passive"))
      (node (ref "JP5") (pin "1") (pinfunction "1_1") (pintype "passive"))
      (node (ref "R16") (pin "2") (pinfunction "2_2") (pintype "passive"))
    )
    (net (code "45") (name "Net-(C17-Pad1)") (class "Default")
      (node (ref "C17") (pin "1") (pinfunction "1_1") (pintype "passive"))
      (node (ref "R8") (pin "2") (pinfunction "2_2") (pintype "passive"))
      (node (ref "SW2") (pin "2") (pinfunction "2_2") (pintype "passive"))
    )
    (net (code "46") (name "Net-(C21-Pad2)") (class "Default")
      (node (ref "C21") (pin "2") (pinfunction "2_2") (pintype "passive"))
      (node (ref "R10") (pin "1") (pinfunction "1_1") (pintype "passive"))
    )
    (net (code "47") (name "Net-(C23-Pad2)") (class "Default")
      (node (ref "C23") (pin "2") (pinfunction "2_2") (pintype "passive"))
      (node (ref "R11") (pin "1") (pinfunction "1_1") (pintype "passive"))
    )
    (net (code "48") (name "Net-(C24-Pad2)") (class "Default")
      (node (ref "C24") (pin "2") (pinfunction "2_2") (pintype "passive"))
      (node (ref "R12") (pin "1") (pinfunction "1_1") (pintype "passive"))
    )
    (net (code "49") (name "Net-(C28-Pad1)") (class "Default")
      (node (ref "C28") (pin "1") (pinfunction "1_1") (pintype "passive"))
      (node (ref "R14") (pin "2") (pinfunction "2_2") (pintype "passive"))
      (node (ref "SW3") (pin "2") (pinfunction "2_2") (pintype "passive"))
    )
    (net (code "50") (name "Net-(D1-DO)") (class "Default")
      (node (ref "D1") (pin "2") (pinfunction "DO_2") (pintype "passive"))
      (node (ref "D3") (pin "4") (pinfunction "DI_4") (pintype "passive"))
    )
    (net (code "51") (name "Net-(D2-DI)") (class "Default")
      (node (ref "D2") (pin "4") (pinfunction "DI_4") (pintype "passive"))
      (node (ref "D7") (pin "2") (pinfunction "DO_2") (pintype "passive"))
    )
    (net (code "52") (name "Net-(D2-DO)") (class "Default")
      (node (ref "D2") (pin "2") (pinfunction "DO_2") (pintype "passive"))
      (node (ref "D4") (pin "4") (pinfunction "DI_4") (pintype "passive"))
    )
    (net (code "53") (name "Net-(D3-DO)") (class "Default")
      (node (ref "D3") (pin "2") (pinfunction "DO_2") (pintype "passive"))
      (node (ref "D5") (pin "4") (pinfunction "DI_4") (pintype "passive"))
    )
    (net (code "54") (name "Net-(D4-DO)") (class "Default")
      (node (ref "D4") (pin "2") (pinfunction "DO_2") (pintype "passive"))
      (node (ref "D6") (pin "4") (pinfunction "DI_4") (pintype "passive"))
    )
    (net (code "55") (name "Net-(D5-DO)") (class "Default")
      (node (ref "D5") (pin "2") (pinfunction "DO_2") (pintype "passive"))
      (node (ref "D7") (pin "4") (pinfunction "DI_4") (pintype "passive"))
    )
    (net (code "56") (name "Net-(D6-DO)") (class "Default")
      (node (ref "D6") (pin "2") (pinfunction "DO_2") (pintype "passive"))
      (node (ref "D8") (pin "4") (pinfunction "DI_4") (pintype "passive"))
    )
    (net (code "57") (name "Net-(E1-A)") (class "Default")
      (node (ref "C16") (pin "1") (pinfunction "1_1") (pintype "passive"))
      (node (ref "E1") (pin "1") (pinfunction "A_1") (pintype "passive"))
      (node (ref "F1") (pin "2") (pinfunction "2_2") (pintype "passive"))
      (node (ref "F2") (pin "1") (pinfunction "1_1") (pintype "passive"))
      (node (ref "U2") (pin "26") (pinfunction "VSP_26") (pintype "power_in"))
      (node (ref "U2") (pin "27") (pinfunction "VSP_27") (pintype "power_in"))
      (node (ref "U2") (pin "28") (pinfunction "VSP_28") (pintype "power_in"))
      (node (ref "U2") (pin "3") (pinfunction "VSP_3") (pintype "power_in"))
      (node (ref "U2") (pin "4") (pinfunction "VSP_4") (pintype "power_in"))
      (node (ref "U2") (pin "5") (pinfunction "VSP_5") (pintype "power_in"))
    )
    (net (code "58") (name "Net-(LED1-K)") (class "Default")
      (node (ref "LED1") (pin "2") (pinfunction "K_2") (pintype "passive"))
      (node (ref "R4") (pin "2") (pinfunction "2_2") (pintype "passive"))
    )
    (net (code "59") (name "Net-(LED2-K)") (class "Default")
      (node (ref "LED2") (pin "2") (pinfunction "K_2") (pintype "passive"))
      (node (ref "R5") (pin "2") (pinfunction "2_2") (pintype "passive"))
    )
    (net (code "60") (name "Net-(R6-Pad2)") (class "Default")
      (node (ref "R6") (pin "2") (pinfunction "2_2") (pintype "passive"))
      (node (ref "U2") (pin "8") (pinfunction "LS1_8") (pintype "passive"))
      (node (ref "U2") (pin "9") (pinfunction "LS1_9") (pintype "passive"))
    )
    (net (code "61") (name "Net-(R7-Pad2)") (class "Default")
      (node (ref "R7") (pin "2") (pinfunction "2_2") (pintype "passive"))
      (node (ref "U2") (pin "39") (pinfunction "LS2_39") (pintype "passive"))
      (node (ref "U2") (pin "40") (pinfunction "LS2_40") (pintype "passive"))
    )
    (net (code "62") (name "Net-(R9-Pad2)") (class "Default")
      (node (ref "R9") (pin "2") (pinfunction "2_2") (pintype "passive"))
      (node (ref "U2") (pin "31") (pinfunction "LS3_31") (pintype "passive"))
      (node (ref "U2") (pin "32") (pinfunction "LS3_32") (pintype "passive"))
    )
    (net (code "63") (name "Net-(R20-Pad1)") (class "Default")
      (node (ref "R20") (pin "1") (pinfunction "1_1") (pintype "passive"))
      (node (ref "SP1") (pin "1") (pinfunction "1_1") (pintype "passive"))
    )
    (net (code "64") (name "Net-(R21-Pad1)") (class "Default")
      (node (ref "R21") (pin "1") (pinfunction "1_1") (pintype "passive"))
      (node (ref "SP2") (pin "1") (pinfunction "1_1") (pintype "passive"))
    )
    (net (code "65") (name "Net-(R22-Pad1)") (class "Default")
      (node (ref "R22") (pin "1") (pinfunction "1_1") (pintype "passive"))
      (node (ref "SP3") (pin "1") (pinfunction "1_1") (pintype "passive"))
    )
    (net (code "66") (name "Net-(R23-Pad1)") (class "Default")
      (node (ref "R23") (pin "1") (pinfunction "1_1") (pintype "passive"))
      (node (ref "SP4") (pin "1") (pinfunction "1_1") (pintype "passive"))
    )
    (net (code "67") (name "Net-(U2-BST1)") (class "Default")
      (node (ref "C21") (pin "1") (pinfunction "1_1") (pintype "passive"))
      (node (ref "U2") (pin "10") (pinfunction "BST1_10") (pintype "passive"))
    )
    (net (code "68") (name "Net-(U2-BST2)") (class "Default")
      (node (ref "C23") (pin "1") (pinfunction "1_1") (pintype "passive"))
      (node (ref "U2") (pin "38") (pinfunction "BST2_38") (pintype "passive"))
    )
    (net (code "69") (name "Net-(U2-BST3)") (class "Default")
      (node (ref "C24") (pin "1") (pinfunction "1_1") (pintype "passive"))
      (node (ref "U2") (pin "33") (pinfunction "BST3_33") (pintype "passive"))
    )
    (net (code "70") (name "Net-(U2-VDR1)") (class "Default")
      (node (ref "C19") (pin "2") (pinfunction "2_2") (pintype "passive"))
      (node (ref "U2") (pin "37") (pinfunction "VDR1_37") (pintype "passive"))
    )
    (net (code "71") (name "Net-(U2-VDR2)") (class "Default")
      (node (ref "C22") (pin "2") (pinfunction "2_2") (pintype "passive"))
      (node (ref "U2") (pin "34") (pinfunction "VDR2_34") (pintype "passive"))
    )
    (net (code "72") (name "Net-(USB1-CC1)") (class "Default")
      (node (ref "R2") (pin "1") (pinfunction "1_1") (pintype "passive"))
      (node (ref "USB1") (pin "A5") (pinfunction "CC1_A5") (pintype "passive"))
    )
    (net (code "73") (name "Net-(USB1-CC2)") (class "Default")
      (node (ref "R1") (pin "1") (pinfunction "1_1") (pintype "passive"))
      (node (ref "USB1") (pin "B5") (pinfunction "CC2_B5") (pintype "passive"))
    )
    (net (code "74") (name "unconnected-(D8-DO-Pad2)") (class "Default")
      (node (ref "D8") (pin "2") (pinfunction "DO_2") (pintype "passive"))
    )
    (net (code "75") (name "unconnected-(U1-PA0-WKUP-Pad14)") (class "Default")
      (node (ref "U1") (pin "14") (pinfunction "PA0-WKUP_14") (pintype "passive"))
    )
    (net (code "76") (name "unconnected-(U1-PA2-Pad16)") (class "Default")
      (node (ref "U1") (pin "16") (pinfunction "PA2_16") (pintype "passive"))
    )
    (net (code "77") (name "unconnected-(U1-PA6-Pad22)") (class "Default")
      (node (ref "U1") (pin "22") (pinfunction "PA6_22") (pintype "passive"))
    )
    (net (code "78") (name "unconnected-(U1-PA15-Pad50)") (class "Default")
      (node (ref "U1") (pin "50") (pinfunction "PA15_50") (pintype "passive"))
    )
    (net (code "79") (name "unconnected-(U1-PB1-Pad27)") (class "Default")
      (node (ref "U1") (pin "27") (pinfunction "PB1_27") (pintype "passive"))
    )
    (net (code "80") (name "unconnected-(U1-PB2-BOOT1-Pad28)") (class "Default")
      (node (ref "U1") (pin "28") (pinfunction "PB2-BOOT1_28") (pintype "passive"))
    )
    (net (code "81") (name "unconnected-(U1-PB3-Pad55)") (class "Default")
      (node (ref "U1") (pin "55") (pinfunction "PB3_55") (pintype "passive"))
    )
    (net (code "82") (name "unconnected-(U1-PB4-Pad56)") (class "Default")
      (node (ref "U1") (pin "56") (pinfunction "PB4_56") (pintype "passive"))
    )
    (net (code "83") (name "unconnected-(U1-PB5-Pad57)") (class "Default")
      (node (ref "U1") (pin "57") (pinfunction "PB5_57") (pintype "passive"))
    )
    (net (code "84") (name "unconnected-(U1-PB8-Pad61)") (class "Default")
      (node (ref "U1") (pin "61") (pinfunction "PB8_61") (pintype "passive"))
    )
    (net (code "85") (name "unconnected-(U1-PB9-Pad62)") (class "Default")
      (node (ref "U1") (pin "62") (pinfunction "PB9_62") (pintype "passive"))
    )
    (net (code "86") (name "unconnected-(U1-PB10-Pad29)") (class "Default")
      (node (ref "U1") (pin "29") (pinfunction "PB10_29") (pintype "passive"))
    )
    (net (code "87") (name "unconnected-(U1-PB11-Pad30)") (class "Default")
      (node (ref "U1") (pin "30") (pinfunction "PB11_30") (pintype "passive"))
    )
    (net (code "88") (name "unconnected-(U1-PC5-Pad25)") (class "Default")
      (node (ref "U1") (pin "25") (pinfunction "PC5_25") (pintype "passive"))
    )
    (net (code "89") (name "unconnected-(U1-PC7-Pad38)") (class "Default")
      (node (ref "U1") (pin "38") (pinfunction "PC7_38") (pintype "passive"))
    )
    (net (code "90") (name "unconnected-(U1-PC8-Pad39)") (class "Default")
      (node (ref "U1") (pin "39") (pinfunction "PC8_39") (pintype "passive"))
    )
    (net (code "91") (name "unconnected-(U1-PC9-Pad40)") (class "Default")
      (node (ref "U1") (pin "40") (pinfunction "PC9_40") (pintype "passive"))
    )
    (net (code "92") (name "unconnected-(U1-PC12-Pad53)") (class "Default")
      (node (ref "U1") (pin "53") (pinfunction "PC12_53") (pintype "passive"))
    )
    (net (code "93") (name "unconnected-(U1-PC13-TAMPER-RTC-Pad2)") (class "Default")
      (node (ref "U1") (pin "2") (pinfunction "PC13-TAMPER-RTC_2") (pintype "passive"))
    )
    (net (code "94") (name "unconnected-(U1-PC14-OSC32-IN-Pad3)") (class "Default")
      (node (ref "U1") (pin "3") (pinfunction "PC14-OSC32-IN_3") (pintype "passive"))
    )
    (net (code "95") (name "unconnected-(U1-PC15-OSC32-OUT-Pad4)") (class "Default")
      (node (ref "U1") (pin "4") (pinfunction "PC15-OSC32-OUT_4") (pintype "passive"))
    )
    (net (code "96") (name "unconnected-(U1-PD2-Pad54)") (class "Default")
      (node (ref "U1") (pin "54") (pinfunction "PD2_54") (pintype "passive"))
    )
    (net (code "97") (name "unconnected-(USB1-SBU1-PadA8)") (class "Default")
      (node (ref "USB1") (pin "A8") (pinfunction "SBU1_A8") (pintype "passive+no_connect"))
    )
    (net (code "98") (name "unconnected-(USB1-SBU2-PadB8)") (class "Default")
      (node (ref "USB1") (pin "B8") (pinfunction "SBU2_B8") (pintype "passive+no_connect"))
    )
  )
)
